# Rev_A_Daughter_Board.net
KiCad netlist of a schematic drawn in EAGLE
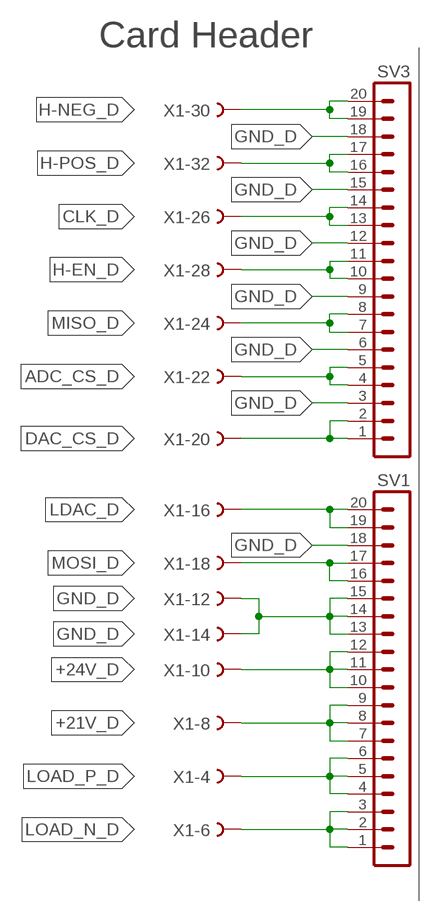
[diagram p0: schematic, sheet 1]

(export (version "E")
  (design (tool "Eeschema 10.0.6"))
  (components
    (comp (ref "SV1")
      (value "MA20-1")
      (footprint "eagle-import:MA20-1")
      (libsource (lib "eagle-import") (part "MA20-1"))
    )
    (comp (ref "SV3")
      (value "MA20-1")
      (footprint "eagle-import:MA20-1")
      (libsource (lib "eagle-import") (part "MA20-1"))
    )
    (comp (ref "X1")
      (value "FH15")
      (footprint "eagle-import:FH15")
      (libsource (lib "eagle-import") (part "FH15"))
    )
  )
  (nets
    (net (code "1") (name "+21V_D") (class "Default")
      (node (ref "SV1") (pin "7") (pinfunction "7_7") (pintype "passive"))
      (node (ref "SV1") (pin "8") (pinfunction "8_8") (pintype "passive"))
      (node (ref "SV1") (pin "9") (pinfunction "9_9") (pintype "passive"))
      (node (ref "X1") (pin "8") (pinfunction "B_8") (pintype "passive"))
    )
    (net (code "2") (name "+24V_D") (class "Default")
      (node (ref "SV1") (pin "10") (pinfunction "10_10") (pintype "passive"))
      (node (ref "SV1") (pin "11") (pinfunction "11_11") (pintype "passive"))
      (node (ref "SV1") (pin "12") (pinfunction "12_12") (pintype "passive"))
      (node (ref "X1") (pin "10") (pinfunction "B_10") (pintype "passive"))
    )
    (net (code "3") (name "ADC_CS_D") (class "Default")
      (node (ref "SV3") (pin "4") (pinfunction "4_4") (pintype "passive"))
      (node (ref "SV3") (pin "5") (pinfunction "5_5") (pintype "passive"))
      (node (ref "X1") (pin "22") (pinfunction "B_22") (pintype "passive"))
    )
    (net (code "4") (name "CLK_D") (class "Default")
      (node (ref "SV3") (pin "13") (pinfunction "13_13") (pintype "passive"))
      (node (ref "SV3") (pin "14") (pinfunction "14_14") (pintype "passive"))
      (node (ref "X1") (pin "26") (pinfunction "B_26") (pintype "passive"))
    )
    (net (code "5") (name "DAC_CS_D") (class "Default")
      (node (ref "SV3") (pin "1") (pinfunction "1_1") (pintype "passive"))
      (node (ref "SV3") (pin "2") (pinfunction "2_2") (pintype "passive"))
      (node (ref "X1") (pin "20") (pinfunction "B_20") (pintype "passive"))
    )
    (net (code "6") (name "GND_D") (class "Default")
      (node (ref "SV1") (pin "13") (pinfunction "13_13") (pintype "passive"))
      (node (ref "SV1") (pin "14") (pinfunction "14_14") (pintype "passive"))
      (node (ref "SV1") (pin "15") (pinfunction "15_15") (pintype "passive"))
      (node (ref "SV1") (pin "18") (pinfunction "18_18") (pintype "passive"))
      (node (ref "SV3") (pin "12") (pinfunction "12_12") (pintype "passive"))
      (node (ref "SV3") (pin "15") (pinfunction "15_15") (pintype "passive"))
      (node (ref "SV3") (pin "18") (pinfunction "18_18") (pintype "passive"))
      (node (ref "SV3") (pin "3") (pinfunction "3_3") (pintype "passive"))
      (node (ref "SV3") (pin "6") (pinfunction "6_6") (pintype "passive"))
      (node (ref "SV3") (pin "9") (pinfunction "9_9") (pintype "passive"))
      (node (ref "X1") (pin "12") (pinfunction "B_12") (pintype "passive"))
      (node (ref "X1") (pin "14") (pinfunction "B_14") (pintype "passive"))
    )
    (net (code "7") (name "H-EN_D") (class "Default")
      (node (ref "SV3") (pin "10") (pinfunction "10_10") (pintype "passive"))
      (node (ref "SV3") (pin "11") (pinfunction "11_11") (pintype "passive"))
      (node (ref "X1") (pin "28") (pinfunction "B_28") (pintype "passive"))
    )
    (net (code "8") (name "H-NEG_D") (class "Default")
      (node (ref "SV3") (pin "19") (pinfunction "19_19") (pintype "passive"))
      (node (ref "SV3") (pin "20") (pinfunction "20_20") (pintype "passive"))
      (node (ref "X1") (pin "30") (pinfunction "B_30") (pintype "passive"))
    )
    (net (code "9") (name "H-POS_D") (class "Default")
      (node (ref "SV3") (pin "16") (pinfunction "16_16") (pintype "passive"))
      (node (ref "SV3") (pin "17") (pinfunction "17_17") (pintype "passive"))
      (node (ref "X1") (pin "32") (pinfunction "B_32") (pintype "passive"))
    )
    (net (code "10") (name "LDAC_D") (class "Default")
      (node (ref "SV1") (pin "19") (pinfunction "19_19") (pintype "passive"))
      (node (ref "SV1") (pin "20") (pinfunction "20_20") (pintype "passive"))
      (node (ref "X1") (pin "16") (pinfunction "B_16") (pintype "passive"))
    )
    (net (code "11") (name "LOAD_N_D") (class "Default")
      (node (ref "SV1") (pin "1") (pinfunction "1_1") (pintype "passive"))
      (node (ref "SV1") (pin "2") (pinfunction "2_2") (pintype "passive"))
      (node (ref "SV1") (pin "3") (pinfunction "3_3") (pintype "passive"))
      (node (ref "X1") (pin "6") (pinfunction "B_6") (pintype "passive"))
    )
    (net (code "12") (name "LOAD_P_D") (class "Default")
      (node (ref "SV1") (pin "4") (pinfunction "4_4") (pintype "passive"))
      (node (ref "SV1") (pin "5") (pinfunction "5_5") (pintype "passive"))
      (node (ref "SV1") (pin "6") (pinfunction "6_6") (pintype "passive"))
      (node (ref "X1") (pin "4") (pinfunction "B_4") (pintype "passive"))
    )
    (net (code "13") (name "MISO_D") (class "Default")
      (node (ref "SV3") (pin "7") (pinfunction "7_7") (pintype "passive"))
      (node (ref "SV3") (pin "8") (pinfunction "8_8") (pintype "passive"))
      (node (ref "X1") (pin "24") (pinfunction "B_24") (pintype "passive"))
    )
    (net (code "14") (name "MOSI_D") (class "Default")
      (node (ref "SV1") (pin "16") (pinfunction "16_16") (pintype "passive"))
      (node (ref "SV1") (pin "17") (pinfunction "17_17") (pintype "passive"))
      (node (ref "X1") (pin "18") (pinfunction "B_18") (pintype "passive"))
    )
  )
)
